# PSU.net
KiCad netlist of a schematic drawn in Altium Designer
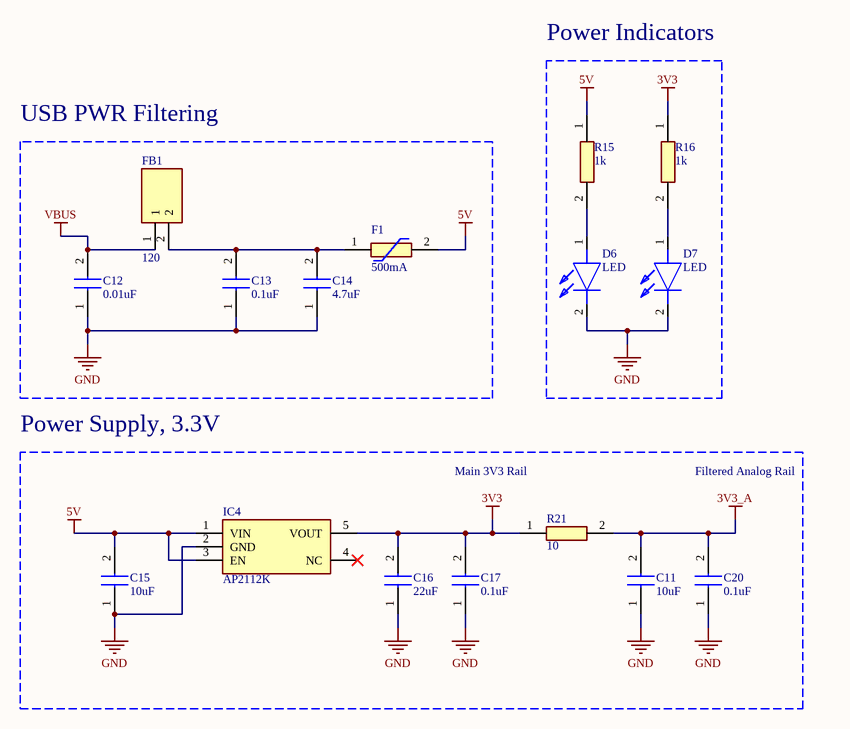
[diagram p0: PSU.SchDoc]

(export (version "E")
  (design (tool "Eeschema 10.0.6"))
  (components
    (comp (ref "C11")
      (value "10uF")
      (footprint "PcbLib1:CAPC2012X140N")
      (description "Capacitor")
      (fields (field (name "MANUFACTURER_PART_NUMBER") "C0805C106K8PACTU-2.5"))
      (libsource (lib "Schlib1") (part "10uF Capacitor 0805"))
    )
    (comp (ref "C12")
      (value "0.01uF")
      (footprint "SamacSys:C0805")
      (description "Capacitor")
      (fields (field (name "MANUFACTURER_PART_NUMBER") "C0805C103K1RECTU"))
      (libsource (lib "Schlib1") (part "0.01uF Capacitor 0805"))
    )
    (comp (ref "C13")
      (value "0.1uF")
      (footprint "SamacSys:CAPC2012X88N")
      (description "Capacitor")
      (fields (field (name "MANUFACTURER_PART_NUMBER") "C0805C104K5RAC-TU"))
      (libsource (lib "Schlib1") (part "0.1uF Capacitor 0805"))
    )
    (comp (ref "C14")
      (value "4.7uF")
      (footprint "SamacSys:C0805")
      (description "Capacitor")
      (fields
        (field (name "MANUFACTURER_PART_NUMBER") "C0805X475M8RACTU")
        (field (name "MOUSER PART NUMBER") "80-C0805X475M8R")
      )
      (libsource (lib "Schlib1") (part "4.7uF Capacitor 0805"))
    )
    (comp (ref "C15")
      (value "10uF")
      (footprint "SamacSys:CAPC2012X140N")
      (description "Capacitor")
      (fields (field (name "MANUFACTURER_PART_NUMBER") "C0805C106K8PACTU-2.5"))
      (libsource (lib "Schlib1") (part "10uF Capacitor 0805"))
    )
    (comp (ref "C16")
      (value "22uF")
      (footprint "SamacSys:C0805")
      (description "Capacitor")
      (fields
        (field (name "MANUFACTURER_PART_NUMBER") "C0805C226M8PAC7210")
        (field (name "MOUSER PART NUMBER") "80-C0805C226M8P7210")
      )
      (libsource (lib "Schlib1") (part "22uF Capacitor 0805"))
    )
    (comp (ref "C17")
      (value "0.1uF")
      (footprint "SamacSys:CAPC2012X88N")
      (description "Capacitor")
      (fields (field (name "MANUFACTURER_PART_NUMBER") "C0805C104K5RAC-TU"))
      (libsource (lib "Schlib1") (part "0.1uF Capacitor 0805"))
    )
    (comp (ref "C20")
      (value "0.1uF")
      (footprint "PcbLib1:CAPC2012X88N")
      (description "Capacitor")
      (fields (field (name "MANUFACTURER_PART_NUMBER") "C0805C104K5RAC-TU"))
      (libsource (lib "Schlib1") (part "0.1uF Capacitor 0805"))
    )
    (comp (ref "D6")
      (value "LED")
      (footprint "SamacSys:APT2012SECKJ3PRV")
      (fields
        (field (name "MANUFACTURER_PART_NUMBER") "APT2012SECK/J3-PRV")
        (field (name "MOUSER PART NUMBER") "604-APT2012SECKJ3PRV")
      )
      (libsource (lib "Schlib1") (part "Orange LED"))
    )
    (comp (ref "D7")
      (value "LED")
      (footprint "SamacSys:APT2012SECKJ3PRV")
      (fields
        (field (name "MANUFACTURER_PART_NUMBER") "APT2012SECK/J3-PRV")
        (field (name "MOUSER PART NUMBER") "604-APT2012SECKJ3PRV")
      )
      (libsource (lib "Schlib1") (part "Orange LED"))
    )
    (comp (ref "F1")
      (value "500mA")
      (footprint "SamacSys:1206L05015YR")
      (description "Resettable Fuse")
      (fields
        (field (name "MANUFACTURER_PART_NUMBER") "1206L050YR")
        (field (name "MOUSER PART NUMBER") "576-1206L050YR")
      )
      (libsource (lib "Schlib1") (part "500mA Fuse"))
    )
    (comp (ref "FB1")
      (value "120")
      (footprint "SamacSys:BLM21AG102BH1J")
      (description "Filter")
      (fields
        (field (name "MANUFACTURER_PART_NUMBER") "BLM21PG121SN1D")
        (field (name "MOUSER PART NUMBER") "81-BLM21PG121SN1D")
      )
      (libsource (lib "Schlib1") (part "120 Ferrite Bead"))
    )
    (comp (ref "IC4")
      (value "AP2112K")
      (footprint "SamacSys:SOT95P285X140-5N")
      (description "Integrated Circuit")
      (fields
        (field (name "MANUFACTURER_PART_NUMBER") "AP2112K-3.3TRG1")
        (field (name "MOUSER PART NUMBER") "621-AP2112K-3.3TRG1")
      )
      (libsource (lib "Schlib1") (part "LDO"))
    )
    (comp (ref "R15")
      (value "1k")
      (footprint "SamacSys:RESC2012X60N")
      (description "Resistor")
      (fields
        (field (name "MANUFACTURER_PART_NUMBER") "RC0805FR-071KL")
        (field (name "MOUSER PART NUMBER") "603-RC0805FR-071KL")
      )
      (libsource (lib "Schlib1") (part "1k Resistor"))
    )
    (comp (ref "R16")
      (value "1k")
      (footprint "SamacSys:RESC2012X60N")
      (description "Resistor")
      (fields
        (field (name "MANUFACTURER_PART_NUMBER") "RC0805FR-071KL")
        (field (name "MOUSER PART NUMBER") "603-RC0805FR-071KL")
      )
      (libsource (lib "Schlib1") (part "1k Resistor"))
    )
    (comp (ref "R21")
      (value "10")
      (footprint "PcbLib1:RESC2012X50N")
      (description "Resistor")
      (fields
        (field (name "MANUFACTURER_PART_NUMBER") "CRCW080510R0FKEA")
        (field (name "MOUSER PART NUMBER") "71-CRCW0805-10-E3")
      )
      (libsource (lib "Schlib1") (part "10 Resistor 0805"))
    )
  )
  (nets
    (net (code "1") (name "3V3") (class "Default")
      (node (ref "C16") (pin "2") (pinfunction "2_2") (pintype "passive"))
      (node (ref "C17") (pin "2") (pinfunction "2_2") (pintype "passive"))
      (node (ref "IC4") (pin "5") (pinfunction "VOUT_5") (pintype "passive"))
      (node (ref "R16") (pin "1") (pinfunction "1_1") (pintype "passive"))
      (node (ref "R21") (pin "1") (pinfunction "1_1") (pintype "passive"))
    )
    (net (code "2") (name "3V3_A") (class "Default")
      (node (ref "C11") (pin "2") (pinfunction "2_2") (pintype "passive"))
      (node (ref "C20") (pin "2") (pinfunction "2_2") (pintype "passive"))
      (node (ref "R21") (pin "2") (pinfunction "2_2") (pintype "passive"))
    )
    (net (code "3") (name "5V") (class "Default")
      (node (ref "C15") (pin "2") (pinfunction "2_2") (pintype "passive"))
      (node (ref "F1") (pin "2") (pinfunction "2_2") (pintype "passive"))
      (node (ref "IC4") (pin "1") (pinfunction "VIN_1") (pintype "passive"))
      (node (ref "IC4") (pin "3") (pinfunction "EN_3") (pintype "passive"))
      (node (ref "R15") (pin "1") (pinfunction "1_1") (pintype "passive"))
    )
    (net (code "4") (name "GND") (class "Default")
      (node (ref "C11") (pin "1") (pinfunction "1_1") (pintype "passive"))
      (node (ref "C12") (pin "1") (pinfunction "1_1") (pintype "passive"))
      (node (ref "C13") (pin "1") (pinfunction "1_1") (pintype "passive"))
      (node (ref "C14") (pin "1") (pinfunction "1_1") (pintype "passive"))
      (node (ref "C15") (pin "1") (pinfunction "1_1") (pintype "passive"))
      (node (ref "C16") (pin "1") (pinfunction "1_1") (pintype "passive"))
      (node (ref "C17") (pin "1") (pinfunction "1_1") (pintype "passive"))
      (node (ref "C20") (pin "1") (pinfunction "1_1") (pintype "passive"))
      (node (ref "D6") (pin "2") (pinfunction "K_2") (pintype "passive"))
      (node (ref "D7") (pin "2") (pinfunction "K_2") (pintype "passive"))
      (node (ref "IC4") (pin "2") (pinfunction "GND_2") (pintype "passive"))
    )
    (net (code "5") (name "Net-(C13-Pad2)") (class "Default")
      (node (ref "C13") (pin "2") (pinfunction "2_2") (pintype "passive"))
      (node (ref "C14") (pin "2") (pinfunction "2_2") (pintype "passive"))
      (node (ref "F1") (pin "1") (pinfunction "1_1") (pintype "passive"))
      (node (ref "FB1") (pin "2") (pinfunction "2_2") (pintype "passive"))
    )
    (net (code "6") (name "Net-(D6-A)") (class "Default")
      (node (ref "D6") (pin "1") (pinfunction "A_1") (pintype "passive"))
      (node (ref "R15") (pin "2") (pinfunction "2_2") (pintype "passive"))
    )
    (net (code "7") (name "Net-(D7-A)") (class "Default")
      (node (ref "D7") (pin "1") (pinfunction "A_1") (pintype "passive"))
      (node (ref "R16") (pin "2") (pinfunction "2_2") (pintype "passive"))
    )
    (net (code "8") (name "VBUS") (class "Default")
      (node (ref "C12") (pin "2") (pinfunction "2_2") (pintype "passive"))
      (node (ref "FB1") (pin "1") (pinfunction "1_1") (pintype "passive"))
    )
    (net (code "9") (name "unconnected-(IC4-NC-Pad4)") (class "Default")
      (node (ref "IC4") (pin "4") (pinfunction "NC_4") (pintype "passive+no_connect"))
    )
  )
)
